# 8channelrelaydriver_throughole.net
KiCad netlist of a schematic drawn in EAGLE
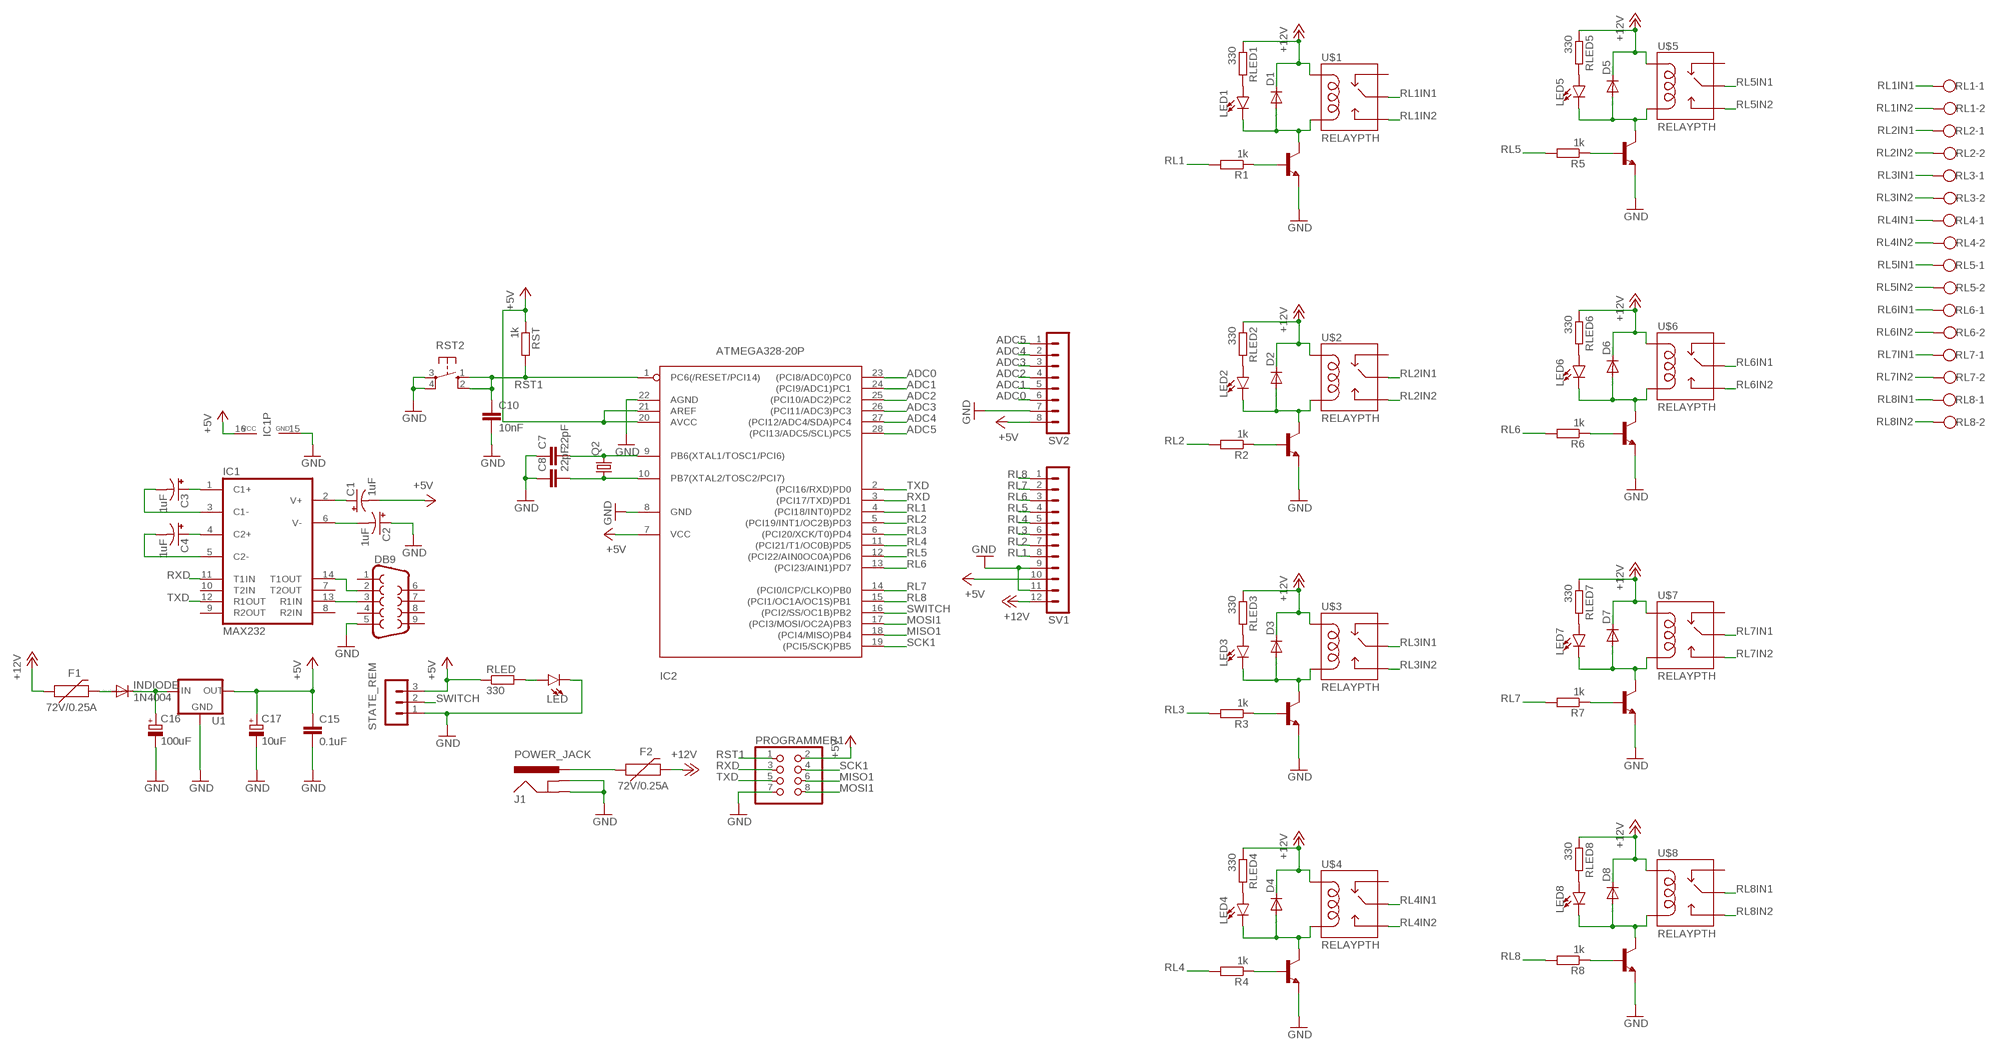
[diagram p0: schematic, sheet 1]

(export (version "E")
  (design (tool "Eeschema 10.0.6"))
  (components
    (comp (ref "C1")
      (value "1uF")
      (footprint "eagle-import:E2,5-6")
      (libsource (lib "eagle-import") (part "CPOL-USE2.5-6"))
    )
    (comp (ref "C2")
      (value "1uF")
      (footprint "eagle-import:E2,5-6")
      (libsource (lib "eagle-import") (part "CPOL-USE2.5-6"))
    )
    (comp (ref "C3")
      (value "1uF")
      (footprint "eagle-import:E2,5-6")
      (libsource (lib "eagle-import") (part "CPOL-USE2.5-6"))
    )
    (comp (ref "C4")
      (value "1uF")
      (footprint "eagle-import:E2,5-6")
      (libsource (lib "eagle-import") (part "CPOL-USE2.5-6"))
    )
    (comp (ref "C7")
      (value "22pF")
      (footprint "eagle-import:C025-025X050")
      (libsource (lib "eagle-import") (part "C-EU025-025X050"))
    )
    (comp (ref "C8")
      (value "22pF")
      (footprint "eagle-import:C025-025X050")
      (libsource (lib "eagle-import") (part "C-EU025-025X050"))
    )
    (comp (ref "C10")
      (value "10nF")
      (footprint "eagle-import:C050-025X075")
      (libsource (lib "eagle-import") (part "C-EU050-025X075"))
    )
    (comp (ref "C15")
      (value "0.1uF")
      (footprint "eagle-import:C050-025X075")
      (libsource (lib "eagle-import") (part "C-EU050-025X075"))
    )
    (comp (ref "C16")
      (value "100uF")
      (footprint "eagle-import:E2,5-6")
      (libsource (lib "eagle-import") (part "CPOL-EUE2.5-6"))
    )
    (comp (ref "C17")
      (value "10uF")
      (footprint "eagle-import:E2,5-6")
      (libsource (lib "eagle-import") (part "CPOL-EUE2.5-6"))
    )
    (comp (ref "D1")
      (value "1N4004")
      (footprint "eagle-import:DO41-10")
      (libsource (lib "eagle-import") (part "1N4004"))
    )
    (comp (ref "D2")
      (value "1N4004")
      (footprint "eagle-import:DO41-10")
      (libsource (lib "eagle-import") (part "1N4004"))
    )
    (comp (ref "D3")
      (value "1N4004")
      (footprint "eagle-import:DO41-10")
      (libsource (lib "eagle-import") (part "1N4004"))
    )
    (comp (ref "D4")
      (value "1N4004")
      (footprint "eagle-import:DO41-10")
      (libsource (lib "eagle-import") (part "1N4004"))
    )
    (comp (ref "D5")
      (value "1N4004")
      (footprint "eagle-import:DO41-10")
      (libsource (lib "eagle-import") (part "1N4004"))
    )
    (comp (ref "D6")
      (value "1N4004")
      (footprint "eagle-import:DO41-10")
      (libsource (lib "eagle-import") (part "1N4004"))
    )
    (comp (ref "D7")
      (value "1N4004")
      (footprint "eagle-import:DO41-10")
      (libsource (lib "eagle-import") (part "1N4004"))
    )
    (comp (ref "D8")
      (value "1N4004")
      (footprint "eagle-import:DO41-10")
      (libsource (lib "eagle-import") (part "1N4004"))
    )
    (comp (ref "DB9")
      (value "DB9FEMALE")
      (footprint "eagle-import:DB9")
      (libsource (lib "eagle-import") (part "DB9FEMALE"))
    )
    (comp (ref "F1")
      (value "72V/0.25A")
      (footprint "eagle-import:PTH")
      (libsource (lib "eagle-import") (part "PPTC_PTH"))
    )
    (comp (ref "F2")
      (value "72V/0.25A")
      (footprint "eagle-import:PTH")
      (libsource (lib "eagle-import") (part "PPTC_PTH"))
    )
    (comp (ref "IC1")
      (value "MAX232")
      (footprint "eagle-import:DIL16")
      (fields (field (name "MF") "MAXIM") (field (name "MPN") "MAX232ACPE+"))
      (libsource (lib "eagle-import") (part "MAX232"))
    )
    (comp (ref "IC2")
      (value "ATMEGA328-20P")
      (footprint "eagle-import:DIL28-3")
      (libsource (lib "eagle-import") (part "ATMEGA328P-20"))
    )
    (comp (ref "INDIODE")
      (value "1N4004")
      (footprint "eagle-import:DO41-10")
      (libsource (lib "eagle-import") (part "1N4004"))
    )
    (comp (ref "J1")
      (value "POWER_JACK")
      (footprint "eagle-import:POWER_JACK_PTH")
      (libsource (lib "eagle-import") (part "POWER_JACK"))
    )
    (comp (ref "LED")
      (value "LED5MM")
      (footprint "eagle-import:LED_5MM")
      (libsource (lib "eagle-import") (part "LED5MM"))
    )
    (comp (ref "LED1")
      (value "LED5MM")
      (footprint "eagle-import:LED_5MM")
      (libsource (lib "eagle-import") (part "LED5MM"))
    )
    (comp (ref "LED2")
      (value "LED5MM")
      (footprint "eagle-import:LED_5MM")
      (libsource (lib "eagle-import") (part "LED5MM"))
    )
    (comp (ref "LED3")
      (value "LED5MM")
      (footprint "eagle-import:LED_5MM")
      (libsource (lib "eagle-import") (part "LED5MM"))
    )
    (comp (ref "LED4")
      (value "LED5MM")
      (footprint "eagle-import:LED_5MM")
      (libsource (lib "eagle-import") (part "LED5MM"))
    )
    (comp (ref "LED5")
      (value "LED5MM")
      (footprint "eagle-import:LED_5MM")
      (libsource (lib "eagle-import") (part "LED5MM"))
    )
    (comp (ref "LED6")
      (value "LED5MM")
      (footprint "eagle-import:LED_5MM")
      (libsource (lib "eagle-import") (part "LED5MM"))
    )
    (comp (ref "LED7")
      (value "LED5MM")
      (footprint "eagle-import:LED_5MM")
      (libsource (lib "eagle-import") (part "LED5MM"))
    )
    (comp (ref "LED8")
      (value "LED5MM")
      (footprint "eagle-import:LED_5MM")
      (libsource (lib "eagle-import") (part "LED5MM"))
    )
    (comp (ref "PROGRAMMER1")
      (value "PINHD-2X4")
      (footprint "eagle-import:2X04")
      (libsource (lib "eagle-import") (part "PINHD-2X4"))
    )
    (comp (ref "Q2")
      (value "CRYSTALHC49U70")
      (footprint "eagle-import:HC49U70")
      (libsource (lib "eagle-import") (part "CRYSTALHC49U70"))
    )
    (comp (ref "R1")
      (value "1k")
      (footprint "eagle-import:0207_10")
      (libsource (lib "eagle-import") (part "R-EU_0207/10"))
    )
    (comp (ref "R2")
      (value "1k")
      (footprint "eagle-import:0207_10")
      (libsource (lib "eagle-import") (part "R-EU_0207/10"))
    )
    (comp (ref "R3")
      (value "1k")
      (footprint "eagle-import:0207_10")
      (libsource (lib "eagle-import") (part "R-EU_0207/10"))
    )
    (comp (ref "R4")
      (value "1k")
      (footprint "eagle-import:0207_10")
      (libsource (lib "eagle-import") (part "R-EU_0207/10"))
    )
    (comp (ref "R5")
      (value "1k")
      (footprint "eagle-import:0207_10")
      (libsource (lib "eagle-import") (part "R-EU_0207/10"))
    )
    (comp (ref "R6")
      (value "1k")
      (footprint "eagle-import:0207_10")
      (libsource (lib "eagle-import") (part "R-EU_0207/10"))
    )
    (comp (ref "R7")
      (value "1k")
      (footprint "eagle-import:0207_10")
      (libsource (lib "eagle-import") (part "R-EU_0207/10"))
    )
    (comp (ref "R8")
      (value "1k")
      (footprint "eagle-import:0207_10")
      (libsource (lib "eagle-import") (part "R-EU_0207/10"))
    )
    (comp (ref "RL1")
      (value "W237-102")
      (footprint "eagle-import:W237-102")
      (fields (field (name "MPN") "237-102"))
      (libsource (lib "eagle-import") (part "W237-102"))
    )
    (comp (ref "RL2")
      (value "W237-102")
      (footprint "eagle-import:W237-102")
      (fields (field (name "MPN") "237-102"))
      (libsource (lib "eagle-import") (part "W237-102"))
    )
    (comp (ref "RL3")
      (value "W237-102")
      (footprint "eagle-import:W237-102")
      (fields (field (name "MPN") "237-102"))
      (libsource (lib "eagle-import") (part "W237-102"))
    )
    (comp (ref "RL4")
      (value "W237-102")
      (footprint "eagle-import:W237-102")
      (fields (field (name "MPN") "237-102"))
      (libsource (lib "eagle-import") (part "W237-102"))
    )
    (comp (ref "RL5")
      (value "W237-102")
      (footprint "eagle-import:W237-102")
      (fields (field (name "MPN") "237-102"))
      (libsource (lib "eagle-import") (part "W237-102"))
    )
    (comp (ref "RL6")
      (value "W237-102")
      (footprint "eagle-import:W237-102")
      (fields (field (name "MPN") "237-102"))
      (libsource (lib "eagle-import") (part "W237-102"))
    )
    (comp (ref "RL7")
      (value "W237-102")
      (footprint "eagle-import:W237-102")
      (fields (field (name "MPN") "237-102"))
      (libsource (lib "eagle-import") (part "W237-102"))
    )
    (comp (ref "RL8")
      (value "W237-102")
      (footprint "eagle-import:W237-102")
      (fields (field (name "MPN") "237-102"))
      (libsource (lib "eagle-import") (part "W237-102"))
    )
    (comp (ref "RLED")
      (value "330")
      (footprint "eagle-import:0207_10")
      (libsource (lib "eagle-import") (part "R-EU_0207/10"))
    )
    (comp (ref "RLED1")
      (value "330")
      (footprint "eagle-import:0207_10")
      (libsource (lib "eagle-import") (part "R-EU_0207/10"))
    )
    (comp (ref "RLED2")
      (value "330")
      (footprint "eagle-import:0207_10")
      (libsource (lib "eagle-import") (part "R-EU_0207/10"))
    )
    (comp (ref "RLED3")
      (value "330")
      (footprint "eagle-import:0207_10")
      (libsource (lib "eagle-import") (part "R-EU_0207/10"))
    )
    (comp (ref "RLED4")
      (value "330")
      (footprint "eagle-import:0207_10")
      (libsource (lib "eagle-import") (part "R-EU_0207/10"))
    )
    (comp (ref "RLED5")
      (value "330")
      (footprint "eagle-import:0207_10")
      (libsource (lib "eagle-import") (part "R-EU_0207/10"))
    )
    (comp (ref "RLED6")
      (value "330")
      (footprint "eagle-import:0207_10")
      (libsource (lib "eagle-import") (part "R-EU_0207/10"))
    )
    (comp (ref "RLED7")
      (value "330")
      (footprint "eagle-import:0207_10")
      (libsource (lib "eagle-import") (part "R-EU_0207/10"))
    )
    (comp (ref "RLED8")
      (value "330")
      (footprint "eagle-import:0207_10")
      (libsource (lib "eagle-import") (part "R-EU_0207/10"))
    )
    (comp (ref "RST")
      (value "1k")
      (footprint "eagle-import:0207_10")
      (libsource (lib "eagle-import") (part "R-EU_0207/10"))
    )
    (comp (ref "RST2")
      (value "10-XX")
      (footprint "eagle-import:B3F-10XX")
      (fields (field (name "MPN") "B3F-1000"))
      (libsource (lib "eagle-import") (part "10-XX"))
    )
    (comp (ref "STATE_REM")
      (value "MA03-1")
      (footprint "eagle-import:MA03-1")
      (libsource (lib "eagle-import") (part "MA03-1"))
    )
    (comp (ref "SV1")
      (value "MA12-1")
      (footprint "eagle-import:MA12-1")
      (libsource (lib "eagle-import") (part "MA12-1"))
    )
    (comp (ref "SV2")
      (value "MA08-1")
      (footprint "eagle-import:MA08-1")
      (libsource (lib "eagle-import") (part "MA08-1"))
    )
    (comp (ref "T1")
      (value "BC547")
      (footprint "eagle-import:TO92")
      (libsource (lib "eagle-import") (part "BC547"))
    )
    (comp (ref "T2")
      (value "BC547")
      (footprint "eagle-import:TO92")
      (libsource (lib "eagle-import") (part "BC547"))
    )
    (comp (ref "T3")
      (value "BC547")
      (footprint "eagle-import:TO92")
      (libsource (lib "eagle-import") (part "BC547"))
    )
    (comp (ref "T4")
      (value "BC547")
      (footprint "eagle-import:TO92")
      (libsource (lib "eagle-import") (part "BC547"))
    )
    (comp (ref "T5")
      (value "BC547")
      (footprint "eagle-import:TO92")
      (libsource (lib "eagle-import") (part "BC547"))
    )
    (comp (ref "T6")
      (value "BC547")
      (footprint "eagle-import:TO92")
      (libsource (lib "eagle-import") (part "BC547"))
    )
    (comp (ref "T7")
      (value "BC547")
      (footprint "eagle-import:TO92")
      (libsource (lib "eagle-import") (part "BC547"))
    )
    (comp (ref "T8")
      (value "BC547")
      (footprint "eagle-import:TO92")
      (libsource (lib "eagle-import") (part "BC547"))
    )
    (comp (ref "U$1")
      (value "RELAYPTH")
      (footprint "eagle-import:SRD-05VDC-SL-C")
      (libsource (lib "eagle-import") (part "RELAYPTH"))
    )
    (comp (ref "U$2")
      (value "RELAYPTH")
      (footprint "eagle-import:SRD-05VDC-SL-C")
      (libsource (lib "eagle-import") (part "RELAYPTH"))
    )
    (comp (ref "U$3")
      (value "RELAYPTH")
      (footprint "eagle-import:SRD-05VDC-SL-C")
      (libsource (lib "eagle-import") (part "RELAYPTH"))
    )
    (comp (ref "U$4")
      (value "RELAYPTH")
      (footprint "eagle-import:SRD-05VDC-SL-C")
      (libsource (lib "eagle-import") (part "RELAYPTH"))
    )
    (comp (ref "U$5")
      (value "RELAYPTH")
      (footprint "eagle-import:SRD-05VDC-SL-C")
      (libsource (lib "eagle-import") (part "RELAYPTH"))
    )
    (comp (ref "U$6")
      (value "RELAYPTH")
      (footprint "eagle-import:SRD-05VDC-SL-C")
      (libsource (lib "eagle-import") (part "RELAYPTH"))
    )
    (comp (ref "U$7")
      (value "RELAYPTH")
      (footprint "eagle-import:SRD-05VDC-SL-C")
      (libsource (lib "eagle-import") (part "RELAYPTH"))
    )
    (comp (ref "U$8")
      (value "RELAYPTH")
      (footprint "eagle-import:SRD-05VDC-SL-C")
      (libsource (lib "eagle-import") (part "RELAYPTH"))
    )
    (comp (ref "U1")
      (value "V_REG_78XXSIDE")
      (footprint "eagle-import:78XXL")
      (libsource (lib "eagle-import") (part "V_REG_78XXSIDE"))
    )
  )
  (nets
    (net (code "1") (name "+5V") (class "Default")
      (node (ref "C1") (pin "-") (pinfunction "-_-") (pintype "passive"))
      (node (ref "C15") (pin "1") (pinfunction "1_1") (pintype "passive"))
      (node (ref "C17") (pin "+") (pinfunction "+_+") (pintype "passive"))
      (node (ref "IC1") (pin "16") (pinfunction "VCC_16") (pintype "power_in"))
      (node (ref "IC2") (pin "20") (pinfunction "AVCC_20") (pintype "bidirectional"))
      (node (ref "IC2") (pin "21") (pinfunction "AREF_21") (pintype "bidirectional"))
      (node (ref "IC2") (pin "7") (pinfunction "VCC_7") (pintype "bidirectional"))
      (node (ref "PROGRAMMER1") (pin "2") (pinfunction "2_2") (pintype "passive"))
      (node (ref "RLED") (pin "1") (pinfunction "1_1") (pintype "passive"))
      (node (ref "RST") (pin "1") (pinfunction "1_1") (pintype "passive"))
      (node (ref "STATE_REM") (pin "3") (pinfunction "3_3") (pintype "passive"))
      (node (ref "SV1") (pin "10") (pinfunction "10_10") (pintype "passive"))
      (node (ref "SV2") (pin "8") (pinfunction "8_8") (pintype "passive"))
      (node (ref "U1") (pin "OUT") (pinfunction "OUT_OUT") (pintype "passive"))
    )
    (net (code "2") (name "+12V") (class "Default")
      (node (ref "D1") (pin "C") (pinfunction "C_C") (pintype "passive"))
      (node (ref "D2") (pin "C") (pinfunction "C_C") (pintype "passive"))
      (node (ref "D3") (pin "C") (pinfunction "C_C") (pintype "passive"))
      (node (ref "D4") (pin "C") (pinfunction "C_C") (pintype "passive"))
      (node (ref "D5") (pin "C") (pinfunction "C_C") (pintype "passive"))
      (node (ref "D6") (pin "C") (pinfunction "C_C") (pintype "passive"))
      (node (ref "D7") (pin "C") (pinfunction "C_C") (pintype "passive"))
      (node (ref "D8") (pin "C") (pinfunction "C_C") (pintype "passive"))
      (node (ref "F1") (pin "P$1") (pinfunction "1_P$1") (pintype "bidirectional"))
      (node (ref "F2") (pin "P$2") (pinfunction "2_P$2") (pintype "bidirectional"))
      (node (ref "RLED1") (pin "1") (pinfunction "1_1") (pintype "passive"))
      (node (ref "RLED2") (pin "1") (pinfunction "1_1") (pintype "passive"))
      (node (ref "RLED3") (pin "1") (pinfunction "1_1") (pintype "passive"))
      (node (ref "RLED4") (pin "1") (pinfunction "1_1") (pintype "passive"))
      (node (ref "RLED5") (pin "1") (pinfunction "1_1") (pintype "passive"))
      (node (ref "RLED6") (pin "1") (pinfunction "1_1") (pintype "passive"))
      (node (ref "RLED7") (pin "1") (pinfunction "1_1") (pintype "passive"))
      (node (ref "RLED8") (pin "1") (pinfunction "1_1") (pintype "passive"))
      (node (ref "SV1") (pin "12") (pinfunction "12_12") (pintype "passive"))
      (node (ref "U$1") (pin "COIL1") (pinfunction "COIL1_COIL1") (pintype "bidirectional"))
      (node (ref "U$2") (pin "COIL1") (pinfunction "COIL1_COIL1") (pintype "bidirectional"))
      (node (ref "U$3") (pin "COIL1") (pinfunction "COIL1_COIL1") (pintype "bidirectional"))
      (node (ref "U$4") (pin "COIL1") (pinfunction "COIL1_COIL1") (pintype "bidirectional"))
      (node (ref "U$5") (pin "COIL1") (pinfunction "COIL1_COIL1") (pintype "bidirectional"))
      (node (ref "U$6") (pin "COIL1") (pinfunction "COIL1_COIL1") (pintype "bidirectional"))
      (node (ref "U$7") (pin "COIL1") (pinfunction "COIL1_COIL1") (pintype "bidirectional"))
      (node (ref "U$8") (pin "COIL1") (pinfunction "COIL1_COIL1") (pintype "bidirectional"))
    )
    (net (code "3") (name "/ADC0") (class "Default")
      (node (ref "IC2") (pin "23") (pinfunction "(PCI8/ADC0)PC0_23") (pintype "bidirectional"))
      (node (ref "SV2") (pin "6") (pinfunction "6_6") (pintype "passive"))
    )
    (net (code "4") (name "/ADC1") (class "Default")
      (node (ref "IC2") (pin "24") (pinfunction "(PCI9/ADC1)PC1_24") (pintype "bidirectional"))
      (node (ref "SV2") (pin "5") (pinfunction "5_5") (pintype "passive"))
    )
    (net (code "5") (name "/ADC2") (class "Default")
      (node (ref "IC2") (pin "25") (pinfunction "(PCI10/ADC2)PC2_25") (pintype "bidirectional"))
      (node (ref "SV2") (pin "4") (pinfunction "4_4") (pintype "passive"))
    )
    (net (code "6") (name "/ADC3") (class "Default")
      (node (ref "IC2") (pin "26") (pinfunction "(PCI11/ADC3)PC3_26") (pintype "bidirectional"))
      (node (ref "SV2") (pin "3") (pinfunction "3_3") (pintype "passive"))
    )
    (net (code "7") (name "/ADC4") (class "Default")
      (node (ref "IC2") (pin "27") (pinfunction "(PCI12/ADC4/SDA)PC4_27") (pintype "bidirectional"))
      (node (ref "SV2") (pin "2") (pinfunction "2_2") (pintype "passive"))
    )
    (net (code "8") (name "/ADC5") (class "Default")
      (node (ref "IC2") (pin "28") (pinfunction "(PCI13/ADC5/SCL)PC5_28") (pintype "bidirectional"))
      (node (ref "SV2") (pin "1") (pinfunction "1_1") (pintype "passive"))
    )
    (net (code "9") (name "/MISO1") (class "Default")
      (node (ref "IC2") (pin "18") (pinfunction "(PCI4/MISO)PB4_18") (pintype "bidirectional"))
      (node (ref "PROGRAMMER1") (pin "6") (pinfunction "6_6") (pintype "passive"))
    )
    (net (code "10") (name "/MOSI1") (class "Default")
      (node (ref "IC2") (pin "17") (pinfunction "(PCI3/MOSI/OC2A)PB3_17") (pintype "bidirectional"))
      (node (ref "PROGRAMMER1") (pin "8") (pinfunction "8_8") (pintype "passive"))
    )
    (net (code "11") (name "/RL1") (class "Default")
      (node (ref "IC2") (pin "4") (pinfunction "(PCI18/INT0)PD2_4") (pintype "bidirectional"))
      (node (ref "R1") (pin "2") (pinfunction "2_2") (pintype "passive"))
      (node (ref "SV1") (pin "8") (pinfunction "8_8") (pintype "passive"))
    )
    (net (code "12") (name "/RL1IN1") (class "Default")
      (node (ref "RL1") (pin "1") (pinfunction "KL_1") (pintype "passive"))
      (node (ref "U$1") (pin "SWCOMMON") (pinfunction "SWCOMMON_SWCOMMON") (pintype "bidirectional"))
    )
    (net (code "13") (name "/RL1IN2") (class "Default")
      (node (ref "RL1") (pin "2") (pinfunction "KL_2") (pintype "passive"))
      (node (ref "U$1") (pin "SWOPEN") (pinfunction "SWOPEN_SWOPEN") (pintype "bidirectional"))
    )
    (net (code "14") (name "/RL2") (class "Default")
      (node (ref "IC2") (pin "5") (pinfunction "(PCI19/INT1/OC2B)PD3_5") (pintype "bidirectional"))
      (node (ref "R2") (pin "2") (pinfunction "2_2") (pintype "passive"))
      (node (ref "SV1") (pin "7") (pinfunction "7_7") (pintype "passive"))
    )
    (net (code "15") (name "/RL2IN1") (class "Default")
      (node (ref "RL2") (pin "1") (pinfunction "KL_1") (pintype "passive"))
      (node (ref "U$2") (pin "SWCOMMON") (pinfunction "SWCOMMON_SWCOMMON") (pintype "bidirectional"))
    )
    (net (code "16") (name "/RL2IN2") (class "Default")
      (node (ref "RL2") (pin "2") (pinfunction "KL_2") (pintype "passive"))
      (node (ref "U$2") (pin "SWOPEN") (pinfunction "SWOPEN_SWOPEN") (pintype "bidirectional"))
    )
    (net (code "17") (name "/RL3") (class "Default")
      (node (ref "IC2") (pin "6") (pinfunction "(PCI20/XCK/T0)PD4_6") (pintype "bidirectional"))
      (node (ref "R3") (pin "2") (pinfunction "2_2") (pintype "passive"))
      (node (ref "SV1") (pin "6") (pinfunction "6_6") (pintype "passive"))
    )
    (net (code "18") (name "/RL3IN1") (class "Default")
      (node (ref "RL3") (pin "1") (pinfunction "KL_1") (pintype "passive"))
      (node (ref "U$3") (pin "SWCOMMON") (pinfunction "SWCOMMON_SWCOMMON") (pintype "bidirectional"))
    )
    (net (code "19") (name "/RL3IN2") (class "Default")
      (node (ref "RL3") (pin "2") (pinfunction "KL_2") (pintype "passive"))
      (node (ref "U$3") (pin "SWOPEN") (pinfunction "SWOPEN_SWOPEN") (pintype "bidirectional"))
    )
    (net (code "20") (name "/RL4") (class "Default")
      (node (ref "IC2") (pin "11") (pinfunction "(PCI21/T1/OC0B)PD5_11") (pintype "bidirectional"))
      (node (ref "R4") (pin "2") (pinfunction "2_2") (pintype "passive"))
      (node (ref "SV1") (pin "5") (pinfunction "5_5") (pintype "passive"))
    )
    (net (code "21") (name "/RL4IN1") (class "Default")
      (node (ref "RL4") (pin "1") (pinfunction "KL_1") (pintype "passive"))
      (node (ref "U$4") (pin "SWCOMMON") (pinfunction "SWCOMMON_SWCOMMON") (pintype "bidirectional"))
    )
    (net (code "22") (name "/RL4IN2") (class "Default")
      (node (ref "RL4") (pin "2") (pinfunction "KL_2") (pintype "passive"))
      (node (ref "U$4") (pin "SWOPEN") (pinfunction "SWOPEN_SWOPEN") (pintype "bidirectional"))
    )
    (net (code "23") (name "/RL5") (class "Default")
      (node (ref "IC2") (pin "12") (pinfunction "(PCI22/AIN0OC0A)PD6_12") (pintype "bidirectional"))
      (node (ref "R5") (pin "2") (pinfunction "2_2") (pintype "passive"))
      (node (ref "SV1") (pin "4") (pinfunction "4_4") (pintype "passive"))
    )
    (net (code "24") (name "/RL5IN1") (class "Default")
      (node (ref "RL5") (pin "1") (pinfunction "KL_1") (pintype "passive"))
      (node (ref "U$5") (pin "SWCOMMON") (pinfunction "SWCOMMON_SWCOMMON") (pintype "bidirectional"))
    )
    (net (code "25") (name "/RL5IN2") (class "Default")
      (node (ref "RL5") (pin "2") (pinfunction "KL_2") (pintype "passive"))
      (node (ref "U$5") (pin "SWOPEN") (pinfunction "SWOPEN_SWOPEN") (pintype "bidirectional"))
    )
    (net (code "26") (name "/RL6") (class "Default")
      (node (ref "IC2") (pin "13") (pinfunction "(PCI23/AIN1)PD7_13") (pintype "bidirectional"))
      (node (ref "R6") (pin "2") (pinfunction "2_2") (pintype "passive"))
      (node (ref "SV1") (pin "3") (pinfunction "3_3") (pintype "passive"))
    )
    (net (code "27") (name "/RL6IN1") (class "Default")
      (node (ref "RL6") (pin "1") (pinfunction "KL_1") (pintype "passive"))
      (node (ref "U$6") (pin "SWCOMMON") (pinfunction "SWCOMMON_SWCOMMON") (pintype "bidirectional"))
    )
    (net (code "28") (name "/RL6IN2") (class "Default")
      (node (ref "RL6") (pin "2") (pinfunction "KL_2") (pintype "passive"))
      (node (ref "U$6") (pin "SWOPEN") (pinfunction "SWOPEN_SWOPEN") (pintype "bidirectional"))
    )
    (net (code "29") (name "/RL7") (class "Default")
      (node (ref "IC2") (pin "14") (pinfunction "(PCI0/ICP/CLKO)PB0_14") (pintype "bidirectional"))
      (node (ref "R7") (pin "2") (pinfunction "2_2") (pintype "passive"))
      (node (ref "SV1") (pin "2") (pinfunction "2_2") (pintype "passive"))
    )
    (net (code "30") (name "/RL7IN1") (class "Default")
      (node (ref "RL7") (pin "1") (pinfunction "KL_1") (pintype "passive"))
      (node (ref "U$7") (pin "SWCOMMON") (pinfunction "SWCOMMON_SWCOMMON") (pintype "bidirectional"))
    )
    (net (code "31") (name "/RL7IN2") (class "Default")
      (node (ref "RL7") (pin "2") (pinfunction "KL_2") (pintype "passive"))
      (node (ref "U$7") (pin "SWOPEN") (pinfunction "SWOPEN_SWOPEN") (pintype "bidirectional"))
    )
    (net (code "32") (name "/RL8") (class "Default")
      (node (ref "IC2") (pin "15") (pinfunction "(PCI1/OC1A/OC1S)PB1_15") (pintype "bidirectional"))
      (node (ref "R8") (pin "2") (pinfunction "2_2") (pintype "passive"))
      (node (ref "SV1") (pin "1") (pinfunction "1_1") (pintype "passive"))
    )
    (net (code "33") (name "/RL8IN1") (class "Default")
      (node (ref "RL8") (pin "1") (pinfunction "KL_1") (pintype "passive"))
      (node (ref "U$8") (pin "SWCOMMON") (pinfunction "SWCOMMON_SWCOMMON") (pintype "bidirectional"))
    )
    (net (code "34") (name "/RL8IN2") (class "Default")
      (node (ref "RL8") (pin "2") (pinfunction "KL_2") (pintype "passive"))
      (node (ref "U$8") (pin "SWOPEN") (pinfunction "SWOPEN_SWOPEN") (pintype "bidirectional"))
    )
    (net (code "35") (name "/RST1") (class "Default")
      (node (ref "C10") (pin "1") (pinfunction "1_1") (pintype "passive"))
      (node (ref "IC2") (pin "1") (pinfunction "PC6(/RESET/PCI14)_1") (pintype "bidirectional"))
      (node (ref "PROGRAMMER1") (pin "1") (pinfunction "1_1") (pintype "passive"))
      (node (ref "RST") (pin "2") (pinfunction "2_2") (pintype "passive"))
      (node (ref "RST2") (pin "1") (pinfunction "S_1") (pintype "passive"))
      (node (ref "RST2") (pin "2") (pinfunction "S1_2") (pintype "passive"))
    )
    (net (code "36") (name "/RXD") (class "Default")
      (node (ref "IC1") (pin "11") (pinfunction "T1IN_11") (pintype "input"))
      (node (ref "IC2") (pin "3") (pinfunction "(PCI17/TXD)PD1_3") (pintype "bidirectional"))
      (node (ref "PROGRAMMER1") (pin "3") (pinfunction "3_3") (pintype "passive"))
    )
    (net (code "37") (name "/SCK1") (class "Default")
      (node (ref "IC2") (pin "19") (pinfunction "(PCI5/SCK)PB5_19") (pintype "bidirectional"))
      (node (ref "PROGRAMMER1") (pin "4") (pinfunction "4_4") (pintype "passive"))
    )
    (net (code "38") (name "/SWITCH") (class "Default")
      (node (ref "IC2") (pin "16") (pinfunction "(PCI2/SS/OC1B)PB2_16") (pintype "bidirectional"))
      (node (ref "STATE_REM") (pin "2") (pinfunction "2_2") (pintype "passive"))
    )
    (net (code "39") (name "/TXD") (class "Default")
      (node (ref "IC1") (pin "12") (pinfunction "R1OUT_12") (pintype "output"))
      (node (ref "IC2") (pin "2") (pinfunction "(PCI16/RXD)PD0_2") (pintype "bidirectional"))
      (node (ref "PROGRAMMER1") (pin "5") (pinfunction "5_5") (pintype "passive"))
    )
    (net (code "40") (name "GND") (class "Default")
      (node (ref "C10") (pin "2") (pinfunction "2_2") (pintype "passive"))
      (node (ref "C15") (pin "2") (pinfunction "2_2") (pintype "passive"))
      (node (ref "C16") (pin "-") (pinfunction "-_-") (pintype "passive"))
      (node (ref "C17") (pin "-") (pinfunction "-_-") (pintype "passive"))
      (node (ref "C2") (pin "+") (pinfunction "+_+") (pintype "passive"))
      (node (ref "C7") (pin "1") (pinfunction "1_1") (pintype "passive"))
      (node (ref "C8") (pin "1") (pinfunction "1_1") (pintype "passive"))
      (node (ref "DB9") (pin "5") (pinfunction "5_5") (pintype "passive"))
      (node (ref "IC1") (pin "15") (pinfunction "GND_15") (pintype "power_in"))
      (node (ref "IC2") (pin "22") (pinfunction "AGND_22") (pintype "bidirectional"))
      (node (ref "IC2") (pin "8") (pinfunction "GND_8") (pintype "bidirectional"))
      (node (ref "J1") (pin "GND") (pinfunction "GND_GND") (pintype "bidirectional"))
      (node (ref "J1") (pin "GNDBREAK") (pinfunction "GNDBREAK_GNDBREAK") (pintype "bidirectional"))
      (node (ref "LED") (pin "K") (pinfunction "C_K") (pintype "passive"))
      (node (ref "PROGRAMMER1") (pin "7") (pinfunction "7_7") (pintype "passive"))
      (node (ref "RST2") (pin "3") (pinfunction "P_3") (pintype "passive"))
      (node (ref "RST2") (pin "4") (pinfunction "P1_4") (pintype "passive"))
      (node (ref "STATE_REM") (pin "1") (pinfunction "1_1") (pintype "passive"))
      (node (ref "SV1") (pin "11") (pinfunction "11_11") (pintype "passive"))
      (node (ref "SV1") (pin "9") (pinfunction "9_9") (pintype "passive"))
      (node (ref "SV2") (pin "7") (pinfunction "7_7") (pintype "passive"))
      (node (ref "T1") (pin "1") (pinfunction "E_1") (pintype "passive"))
      (node (ref "T2") (pin "1") (pinfunction "E_1") (pintype "passive"))
      (node (ref "T3") (pin "1") (pinfunction "E_1") (pintype "passive"))
      (node (ref "T4") (pin "1") (pinfunction "E_1") (pintype "passive"))
      (node (ref "T5") (pin "1") (pinfunction "E_1") (pintype "passive"))
      (node (ref "T6") (pin "1") (pinfunction "E_1") (pintype "passive"))
      (node (ref "T7") (pin "1") (pinfunction "E_1") (pintype "passive"))
      (node (ref "T8") (pin "1") (pinfunction "E_1") (pintype "passive"))
      (node (ref "U1") (pin "GND") (pinfunction "GND_GND") (pintype "input"))
    )
    (net (code "41") (name "Net-(C16-Pad+)") (class "Default")
      (node (ref "C16") (pin "+") (pinfunction "+_+") (pintype "passive"))
      (node (ref "INDIODE") (pin "C") (pinfunction "C_C") (pintype "passive"))
      (node (ref "U1") (pin "IN") (pinfunction "IN_IN") (pintype "input"))
    )
    (net (code "42") (name "Net-(F1-2)") (class "Default")
      (node (ref "F1") (pin "P$2") (pinfunction "2_P$2") (pintype "bidirectional"))
      (node (ref "INDIODE") (pin "A") (pinfunction "A_A") (pintype "passive"))
    )
    (net (code "43") (name "Net-(F2-1)") (class "Default")
      (node (ref "F2") (pin "P$1") (pinfunction "1_P$1") (pintype "bidirectional"))
      (node (ref "J1") (pin "PWR") (pinfunction "PWR_PWR") (pintype "bidirectional"))
    )
    (net (code "44") (name "Net-(IC1A-C1+)") (class "Default")
      (node (ref "C3") (pin "+") (pinfunction "+_+") (pintype "passive"))
      (node (ref "IC1") (pin "1") (pinfunction "C1+_1") (pintype "bidirectional"))
    )
    (net (code "45") (name "Net-(IC1A-C1-)") (class "Default")
      (node (ref "C3") (pin "-") (pinfunction "-_-") (pintype "passive"))
      (node (ref "IC1") (pin "3") (pinfunction "C1-_3") (pintype "bidirectional"))
    )
    (net (code "46") (name "Net-(IC1A-C2+)") (class "Default")
      (node (ref "C4") (pin "+") (pinfunction "+_+") (pintype "passive"))
      (node (ref "IC1") (pin "4") (pinfunction "C2+_4") (pintype "bidirectional"))
    )
    (net (code "47") (name "Net-(IC1A-C2-)") (class "Default")
      (node (ref "C4") (pin "-") (pinfunction "-_-") (pintype "passive"))
      (node (ref "IC1") (pin "5") (pinfunction "C2-_5") (pintype "bidirectional"))
    )
    (net (code "48") (name "Net-(IC1A-R1IN)") (class "Default")
      (node (ref "DB9") (pin "3") (pinfunction "3_3") (pintype "passive"))
      (node (ref "IC1") (pin "13") (pinfunction "R1IN_13") (pintype "input"))
    )
    (net (code "49") (name "Net-(IC1A-T1OUT)") (class "Default")
      (node (ref "DB9") (pin "2") (pinfunction "2_2") (pintype "passive"))
      (node (ref "IC1") (pin "14") (pinfunction "T1OUT_14") (pintype "output"))
    )
    (net (code "50") (name "Net-(IC1A-V+)") (class "Default")
      (node (ref "C1") (pin "+") (pinfunction "+_+") (pintype "passive"))
      (node (ref "IC1") (pin "2") (pinfunction "V+_2") (pintype "bidirectional"))
    )
    (net (code "51") (name "Net-(IC1A-V-)") (class "Default")
      (node (ref "C2") (pin "-") (pinfunction "-_-") (pintype "passive"))
      (node (ref "IC1") (pin "6") (pinfunction "V-_6") (pintype "bidirectional"))
    )
    (net (code "52") (name "Net-(IC2-PB6(XTAL1{slash}TOSC1{slash}PCI6))") (class "Default")
      (node (ref "C7") (pin "2") (pinfunction "2_2") (pintype "passive"))
      (node (ref "IC2") (pin "9") (pinfunction "PB6(XTAL1/TOSC1/PCI6)_9") (pintype "bidirectional"))
      (node (ref "Q2") (pin "2") (pinfunction "2_2") (pintype "passive"))
    )
    (net (code "53") (name "Net-(IC2-PB7(XTAL2{slash}TOSC2{slash}PCI7))") (class "Default")
      (node (ref "C8") (pin "2") (pinfunction "2_2") (pintype "passive"))
      (node (ref "IC2") (pin "10") (pinfunction "PB7(XTAL2/TOSC2/PCI7)_10") (pintype "bidirectional"))
      (node (ref "Q2") (pin "1") (pinfunction "1_1") (pintype "passive"))
    )
    (net (code "54") (name "Net-(LED-PadA)") (class "Default")
      (node (ref "LED") (pin "A") (pinfunction "A_A") (pintype "passive"))
      (node (ref "RLED") (pin "2") (pinfunction "2_2") (pintype "passive"))
    )
    (net (code "55") (name "Net-(LED1-C)") (class "Default")
      (node (ref "D1") (pin "A") (pinfunction "A_A") (pintype "passive"))
      (node (ref "LED1") (pin "K") (pinfunction "C_K") (pintype "passive"))
      (node (ref "T1") (pin "3") (pinfunction "C_3") (pintype "passive"))
      (node (ref "U$1") (pin "COIL0") (pinfunction "COIL0_COIL0") (pintype "bidirectional"))
    )
    (net (code "56") (name "Net-(LED1-PadA)") (class "Default")
      (node (ref "LED1") (pin "A") (pinfunction "A_A") (pintype "passive"))
      (node (ref "RLED1") (pin "2") (pinfunction "2_2") (pintype "passive"))
    )
    (net (code "57") (name "Net-(LED2-C)") (class "Default")
      (node (ref "D2") (pin "A") (pinfunction "A_A") (pintype "passive"))
      (node (ref "LED2") (pin "K") (pinfunction "C_K") (pintype "passive"))
      (node (ref "T2") (pin "3") (pinfunction "C_3") (pintype "passive"))
      (node (ref "U$2") (pin "COIL0") (pinfunction "COIL0_COIL0") (pintype "bidirectional"))
    )
    (net (code "58") (name "Net-(LED2-PadA)") (class "Default")
      (node (ref "LED2") (pin "A") (pinfunction "A_A") (pintype "passive"))
      (node (ref "RLED2") (pin "2") (pinfunction "2_2") (pintype "passive"))
    )
    (net (code "59") (name "Net-(LED3-C)") (class "Default")
      (node (ref "D3") (pin "A") (pinfunction "A_A") (pintype "passive"))
      (node (ref "LED3") (pin "K") (pinfunction "C_K") (pintype "passive"))
      (node (ref "T3") (pin "3") (pinfunction "C_3") (pintype "passive"))
      (node (ref "U$3") (pin "COIL0") (pinfunction "COIL0_COIL0") (pintype "bidirectional"))
    )
    (net (code "60") (name "Net-(LED3-PadA)") (class "Default")
      (node (ref "LED3") (pin "A") (pinfunction "A_A") (pintype "passive"))
      (node (ref "RLED3") (pin "2") (pinfunction "2_2") (pintype "passive"))
    )
    (net (code "61") (name "Net-(LED4-C)") (class "Default")
      (node (ref "D4") (pin "A") (pinfunction "A_A") (pintype "passive"))
      (node (ref "LED4") (pin "K") (pinfunction "C_K") (pintype "passive"))
      (node (ref "T4") (pin "3") (pinfunction "C_3") (pintype "passive"))
      (node (ref "U$4") (pin "COIL0") (pinfunction "COIL0_COIL0") (pintype "bidirectional"))
    )
    (net (code "62") (name "Net-(LED4-PadA)") (class "Default")
      (node (ref "LED4") (pin "A") (pinfunction "A_A") (pintype "passive"))
      (node (ref "RLED4") (pin "2") (pinfunction "2_2") (pintype "passive"))
    )
    (net (code "63") (name "Net-(LED5-C)") (class "Default")
      (node (ref "D5") (pin "A") (pinfunction "A_A") (pintype "passive"))
      (node (ref "LED5") (pin "K") (pinfunction "C_K") (pintype "passive"))
      (node (ref "T5") (pin "3") (pinfunction "C_3") (pintype "passive"))
      (node (ref "U$5") (pin "COIL0") (pinfunction "COIL0_COIL0") (pintype "bidirectional"))
    )
    (net (code "64") (name "Net-(LED5-PadA)") (class "Default")
      (node (ref "LED5") (pin "A") (pinfunction "A_A") (pintype "passive"))
      (node (ref "RLED5") (pin "2") (pinfunction "2_2") (pintype "passive"))
    )
    (net (code "65") (name "Net-(LED6-C)") (class "Default")
      (node (ref "D6") (pin "A") (pinfunction "A_A") (pintype "passive"))
      (node (ref "LED6") (pin "K") (pinfunction "C_K") (pintype "passive"))
      (node (ref "T6") (pin "3") (pinfunction "C_3") (pintype "passive"))
      (node (ref "U$6") (pin "COIL0") (pinfunction "COIL0_COIL0") (pintype "bidirectional"))
    )
    (net (code "66") (name "Net-(LED6-PadA)") (class "Default")
      (node (ref "LED6") (pin "A") (pinfunction "A_A") (pintype "passive"))
      (node (ref "RLED6") (pin "2") (pinfunction "2_2") (pintype "passive"))
    )
    (net (code "67") (name "Net-(LED7-C)") (class "Default")
      (node (ref "D7") (pin "A") (pinfunction "A_A") (pintype "passive"))
      (node (ref "LED7") (pin "K") (pinfunction "C_K") (pintype "passive"))
      (node (ref "T7") (pin "3") (pinfunction "C_3") (pintype "passive"))
      (node (ref "U$7") (pin "COIL0") (pinfunction "COIL0_COIL0") (pintype "bidirectional"))
    )
    (net (code "68") (name "Net-(LED7-PadA)") (class "Default")
      (node (ref "LED7") (pin "A") (pinfunction "A_A") (pintype "passive"))
      (node (ref "RLED7") (pin "2") (pinfunction "2_2") (pintype "passive"))
    )
    (net (code "69") (name "Net-(LED8-C)") (class "Default")
      (node (ref "D8") (pin "A") (pinfunction "A_A") (pintype "passive"))
      (node (ref "LED8") (pin "K") (pinfunction "C_K") (pintype "passive"))
      (node (ref "T8") (pin "3") (pinfunction "C_3") (pintype "passive"))
      (node (ref "U$8") (pin "COIL0") (pinfunction "COIL0_COIL0") (pintype "bidirectional"))
    )
    (net (code "70") (name "Net-(LED8-PadA)") (class "Default")
      (node (ref "LED8") (pin "A") (pinfunction "A_A") (pintype "passive"))
      (node (ref "RLED8") (pin "2") (pinfunction "2_2") (pintype "passive"))
    )
    (net (code "71") (name "Net-(T1-B)") (class "Default")
      (node (ref "R1") (pin "1") (pinfunction "1_1") (pintype "passive"))
      (node (ref "T1") (pin "2") (pinfunction "B_2") (pintype "passive"))
    )
    (net (code "72") (name "Net-(T2-B)") (class "Default")
      (node (ref "R2") (pin "1") (pinfunction "1_1") (pintype "passive"))
      (node (ref "T2") (pin "2") (pinfunction "B_2") (pintype "passive"))
    )
    (net (code "73") (name "Net-(T3-B)") (class "Default")
      (node (ref "R3") (pin "1") (pinfunction "1_1") (pintype "passive"))
      (node (ref "T3") (pin "2") (pinfunction "B_2") (pintype "passive"))
    )
    (net (code "74") (name "Net-(T4-B)") (class "Default")
      (node (ref "R4") (pin "1") (pinfunction "1_1") (pintype "passive"))
      (node (ref "T4") (pin "2") (pinfunction "B_2") (pintype "passive"))
    )
    (net (code "75") (name "Net-(T5-B)") (class "Default")
      (node (ref "R5") (pin "1") (pinfunction "1_1") (pintype "passive"))
      (node (ref "T5") (pin "2") (pinfunction "B_2") (pintype "passive"))
    )
    (net (code "76") (name "Net-(T6-B)") (class "Default")
      (node (ref "R6") (pin "1") (pinfunction "1_1") (pintype "passive"))
      (node (ref "T6") (pin "2") (pinfunction "B_2") (pintype "passive"))
    )
    (net (code "77") (name "Net-(T7-B)") (class "Default")
      (node (ref "R7") (pin "1") (pinfunction "1_1") (pintype "passive"))
      (node (ref "T7") (pin "2") (pinfunction "B_2") (pintype "passive"))
    )
    (net (code "78") (name "Net-(T8-B)") (class "Default")
      (node (ref "R8") (pin "1") (pinfunction "1_1") (pintype "passive"))
      (node (ref "T8") (pin "2") (pinfunction "B_2") (pintype "passive"))
    )
    (net (code "79") (name "unconnected-(DB9-Pad1)") (class "Default")
      (node (ref "DB9") (pin "1") (pinfunction "1_1") (pintype "passive"))
    )
    (net (code "80") (name "unconnected-(DB9-Pad4)") (class "Default")
      (node (ref "DB9") (pin "4") (pinfunction "4_4") (pintype "passive"))
    )
    (net (code "81") (name "unconnected-(DB9-Pad6)") (class "Default")
      (node (ref "DB9") (pin "6") (pinfunction "6_6") (pintype "passive"))
    )
    (net (code "82") (name "unconnected-(DB9-Pad7)") (class "Default")
      (node (ref "DB9") (pin "7") (pinfunction "7_7") (pintype "passive"))
    )
    (net (code "83") (name "unconnected-(DB9-Pad8)") (class "Default")
      (node (ref "DB9") (pin "8") (pinfunction "8_8") (pintype "passive"))
    )
    (net (code "84") (name "unconnected-(DB9-Pad9)") (class "Default")
      (node (ref "DB9") (pin "9") (pinfunction "9_9") (pintype "passive"))
    )
    (net (code "85") (name "unconnected-(IC1A-R2IN-Pad8)") (class "Default")
      (node (ref "IC1") (pin "8") (pinfunction "R2IN_8") (pintype "input"))
    )
    (net (code "86") (name "unconnected-(IC1A-R2OUT-Pad9)") (class "Default")
      (node (ref "IC1") (pin "9") (pinfunction "R2OUT_9") (pintype "output"))
    )
    (net (code "87") (name "unconnected-(IC1A-T2IN-Pad10)") (class "Default")
      (node (ref "IC1") (pin "10") (pinfunction "T2IN_10") (pintype "input"))
    )
    (net (code "88") (name "unconnected-(IC1A-T2OUT-Pad7)") (class "Default")
      (node (ref "IC1") (pin "7") (pinfunction "T2OUT_7") (pintype "output"))
    )
    (net (code "89") (name "unconnected-(U$1-SWCLOSE-PadSWCLOSED)") (class "Default")
      (node (ref "U$1") (pin "SWCLOSED") (pinfunction "SWCLOSE_SWCLOSED") (pintype "bidirectional"))
    )
    (net (code "90") (name "unconnected-(U$2-SWCLOSE-PadSWCLOSED)") (class "Default")
      (node (ref "U$2") (pin "SWCLOSED") (pinfunction "SWCLOSE_SWCLOSED") (pintype "bidirectional"))
    )
    (net (code "91") (name "unconnected-(U$3-SWCLOSE-PadSWCLOSED)") (class "Default")
      (node (ref "U$3") (pin "SWCLOSED") (pinfunction "SWCLOSE_SWCLOSED") (pintype "bidirectional"))
    )
    (net (code "92") (name "unconnected-(U$4-SWCLOSE-PadSWCLOSED)") (class "Default")
      (node (ref "U$4") (pin "SWCLOSED") (pinfunction "SWCLOSE_SWCLOSED") (pintype "bidirectional"))
    )
    (net (code "93") (name "unconnected-(U$5-SWCLOSE-PadSWCLOSED)") (class "Default")
      (node (ref "U$5") (pin "SWCLOSED") (pinfunction "SWCLOSE_SWCLOSED") (pintype "bidirectional"))
    )
    (net (code "94") (name "unconnected-(U$6-SWCLOSE-PadSWCLOSED)") (class "Default")
      (node (ref "U$6") (pin "SWCLOSED") (pinfunction "SWCLOSE_SWCLOSED") (pintype "bidirectional"))
    )
    (net (code "95") (name "unconnected-(U$7-SWCLOSE-PadSWCLOSED)") (class "Default")
      (node (ref "U$7") (pin "SWCLOSED") (pinfunction "SWCLOSE_SWCLOSED") (pintype "bidirectional"))
    )
    (net (code "96") (name "unconnected-(U$8-SWCLOSE-PadSWCLOSED)") (class "Default")
      (node (ref "U$8") (pin "SWCLOSED") (pinfunction "SWCLOSE_SWCLOSED") (pintype "bidirectional"))
    )
  )
)
